# Driver.net
KiCad netlist of a schematic drawn in EAGLE
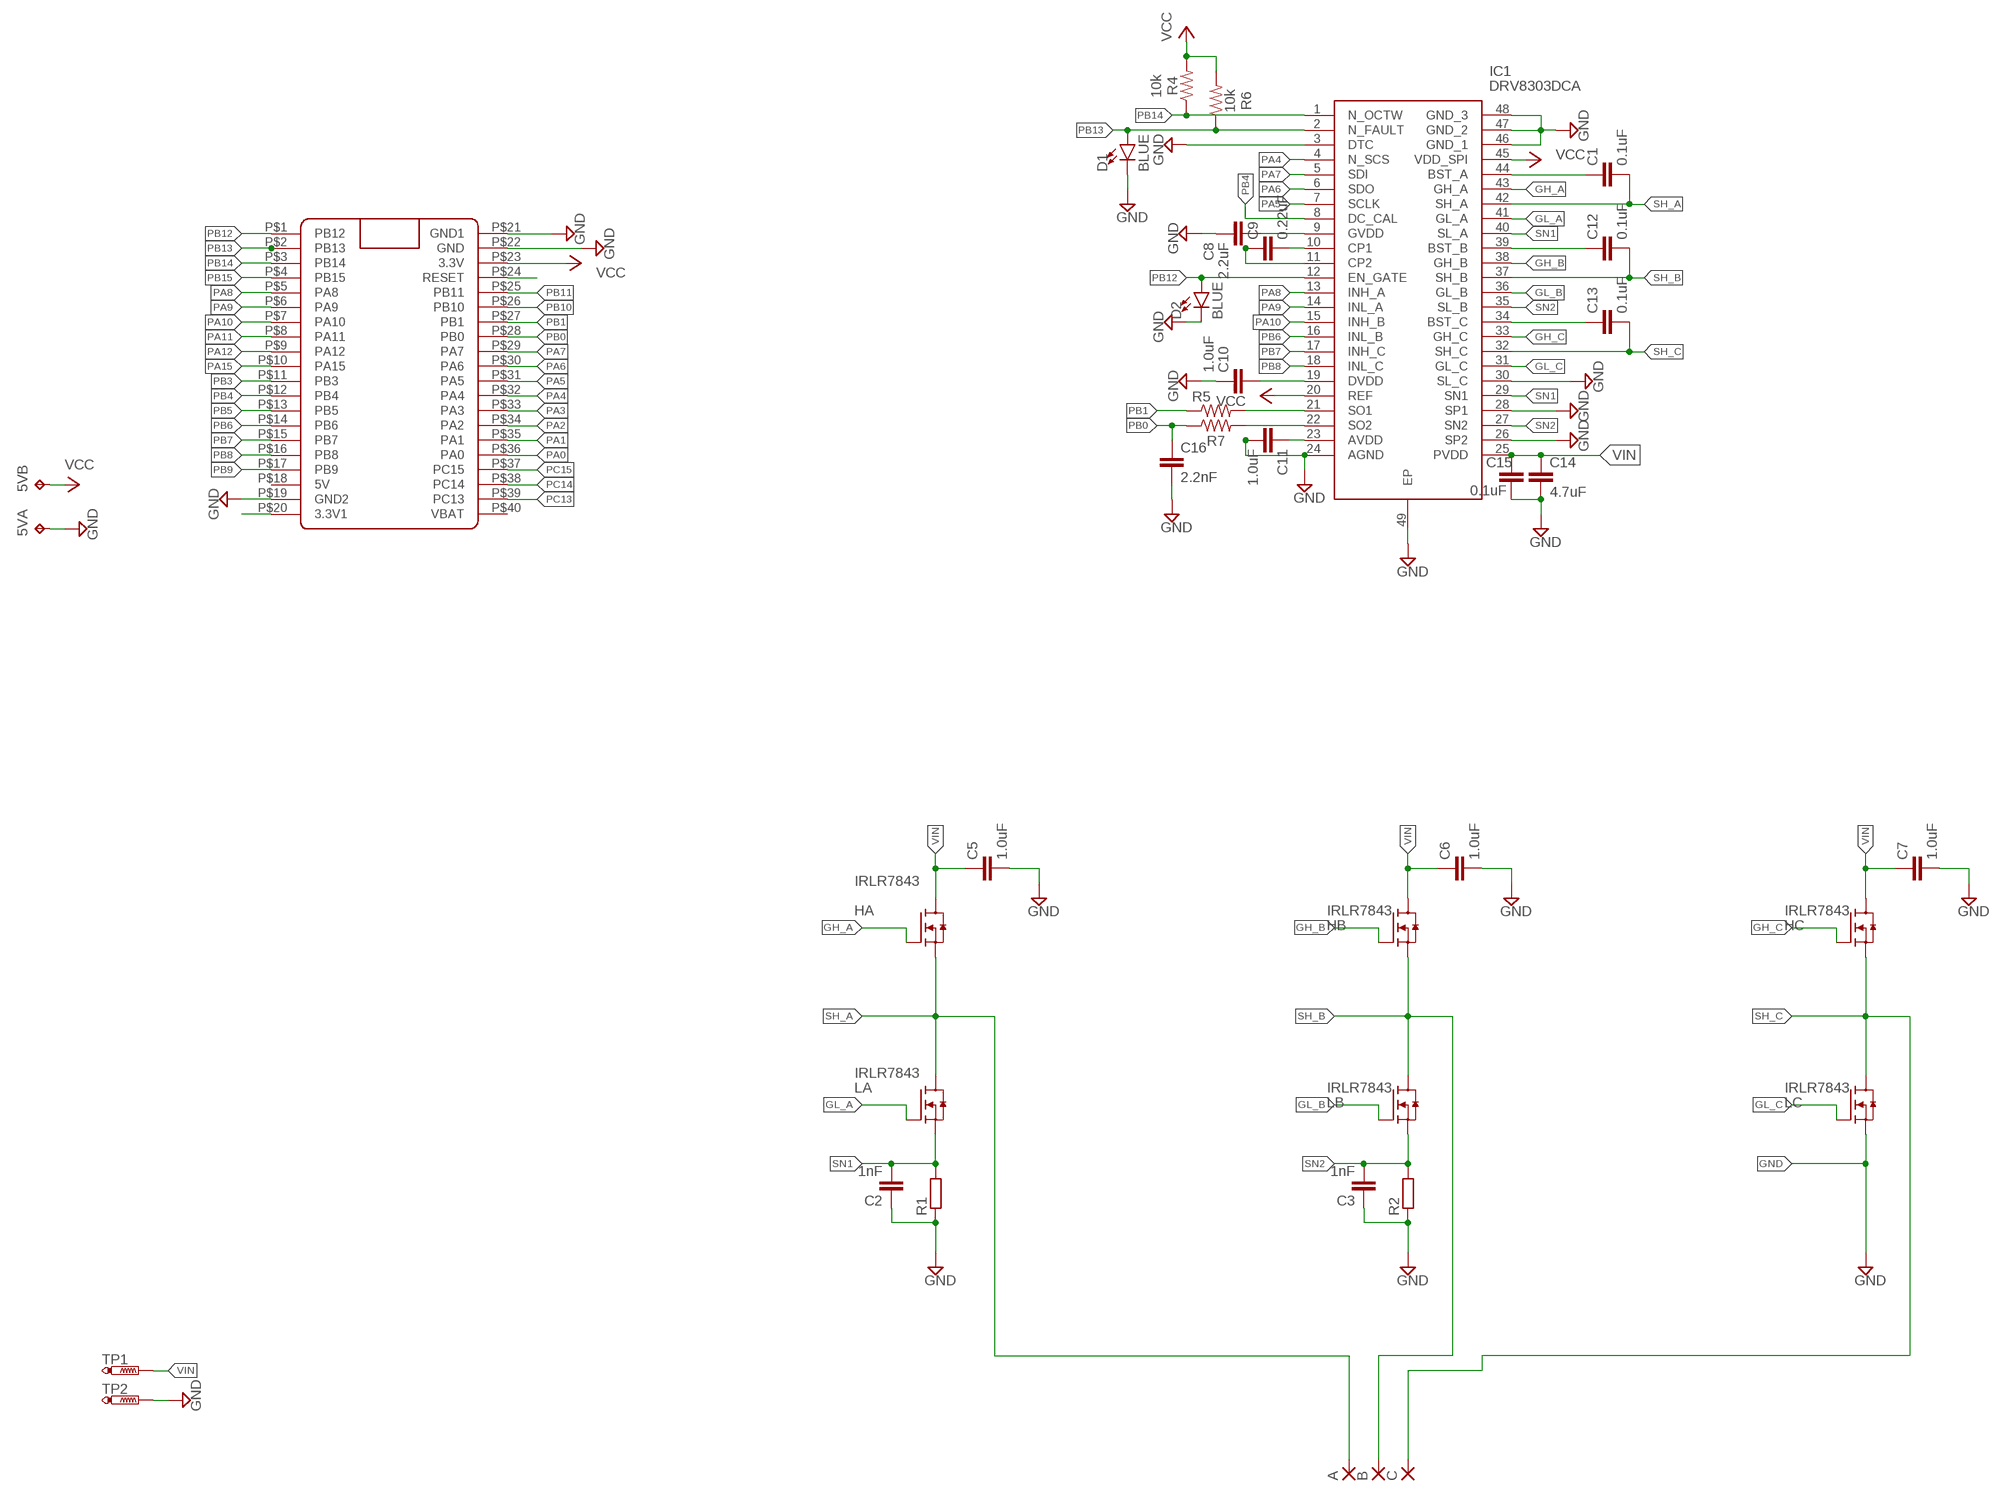
[diagram p0: schematic, sheet 1]

(export (version "E")
  (design (tool "Eeschema 10.0.6"))
  (components
    (comp (ref "5V")
      (value "TP2P2-38-17")
      (footprint "eagle-import:P2-38-17")
      (libsource (lib "eagle-import") (part "TP2P2-38-17"))
    )
    (comp (ref "A")
      (value "SMD5")
      (footprint "eagle-import:SMD2,54-5,08")
      (libsource (lib "eagle-import") (part "SMD5"))
    )
    (comp (ref "B")
      (value "SMD5")
      (footprint "eagle-import:SMD2,54-5,08")
      (libsource (lib "eagle-import") (part "SMD5"))
    )
    (comp (ref "C")
      (value "SMD5")
      (footprint "eagle-import:SMD2,54-5,08")
      (libsource (lib "eagle-import") (part "SMD5"))
    )
    (comp (ref "C1")
      (value "0.1uF")
      (footprint "eagle-import:0603")
      (libsource (lib "eagle-import") (part "0.1UF-0603-25V-(+80/-20%)"))
    )
    (comp (ref "C2")
      (value "1nF")
      (footprint "eagle-import:0603")
      (libsource (lib "eagle-import") (part "1.0NF/1000PF-0603-50V-10%"))
    )
    (comp (ref "C3")
      (value "1nF")
      (footprint "eagle-import:0603")
      (libsource (lib "eagle-import") (part "1.0NF/1000PF-0603-50V-10%"))
    )
    (comp (ref "C5")
      (value "1.0uF")
      (footprint "eagle-import:0603")
      (libsource (lib "eagle-import") (part "1.0UF-0603-16V-10%-X7R"))
    )
    (comp (ref "C6")
      (value "1.0uF")
      (footprint "eagle-import:0603")
      (libsource (lib "eagle-import") (part "1.0UF-0603-16V-10%-X7R"))
    )
    (comp (ref "C7")
      (value "1.0uF")
      (footprint "eagle-import:0603")
      (libsource (lib "eagle-import") (part "1.0UF-0603-16V-10%-X7R"))
    )
    (comp (ref "C8")
      (value "2.2uF")
      (footprint "eagle-import:0603")
      (libsource (lib "eagle-import") (part "2.2UF-0603-10V-20%"))
    )
    (comp (ref "C9")
      (value "0.22uF")
      (footprint "eagle-import:0603")
      (libsource (lib "eagle-import") (part "0.22UF-0603-25V-10%"))
    )
    (comp (ref "C10")
      (value "1.0uF")
      (footprint "eagle-import:0603")
      (libsource (lib "eagle-import") (part "1.0UF-0603-16V-10%"))
    )
    (comp (ref "C11")
      (value "1.0uF")
      (footprint "eagle-import:0603")
      (libsource (lib "eagle-import") (part "1.0UF-0603-16V-10%"))
    )
    (comp (ref "C12")
      (value "0.1uF")
      (footprint "eagle-import:0603")
      (libsource (lib "eagle-import") (part "0.1UF-0603-25V-(+80/-20%)"))
    )
    (comp (ref "C13")
      (value "0.1uF")
      (footprint "eagle-import:0603")
      (libsource (lib "eagle-import") (part "0.1UF-0603-25V-(+80/-20%)"))
    )
    (comp (ref "C14")
      (value "4.7uF")
      (footprint "eagle-import:0603")
      (libsource (lib "eagle-import") (part "4.7UF-0603-35V-(20%)"))
    )
    (comp (ref "C15")
      (value "0.1uF")
      (footprint "eagle-import:0603")
      (libsource (lib "eagle-import") (part "0.1UF-0603-25V-(+80/-20%)"))
    )
    (comp (ref "C16")
      (value "2.2nF")
      (footprint "eagle-import:0603")
      (libsource (lib "eagle-import") (part "2.2NF/2200PF-0603-50V-10%"))
    )
    (comp (ref "D1")
      (value "BLUE")
      (footprint "eagle-import:LED-0603")
      (libsource (lib "eagle-import") (part "LED-BLUE0603"))
    )
    (comp (ref "D2")
      (value "BLUE")
      (footprint "eagle-import:LED-0603")
      (libsource (lib "eagle-import") (part "LED-BLUE0603"))
    )
    (comp (ref "HA")
      (value "IRLR7843")
      (footprint "eagle-import:TO252")
      (libsource (lib "eagle-import") (part "IRLR7843"))
    )
    (comp (ref "HB")
      (value "IRLR7843")
      (footprint "eagle-import:TO252")
      (libsource (lib "eagle-import") (part "IRLR7843"))
    )
    (comp (ref "HC")
      (value "IRLR7843")
      (footprint "eagle-import:TO252")
      (libsource (lib "eagle-import") (part "IRLR7843"))
    )
    (comp (ref "IC1")
      (value "DRV8303DCA")
      (footprint "eagle-import:SOP50P810X120-49N")
      (fields (field (name "MOUSER_PART_NUMBER") "595-DRV8303DCA"))
      (libsource (lib "eagle-import") (part "DRV8303DCA"))
    )
    (comp (ref "LA")
      (value "IRLR7843")
      (footprint "eagle-import:TO252")
      (libsource (lib "eagle-import") (part "IRLR7843"))
    )
    (comp (ref "LB")
      (value "IRLR7843")
      (footprint "eagle-import:TO252")
      (libsource (lib "eagle-import") (part "IRLR7843"))
    )
    (comp (ref "LC")
      (value "IRLR7843")
      (footprint "eagle-import:TO252")
      (libsource (lib "eagle-import") (part "IRLR7843"))
    )
    (comp (ref "R1")
      (value "R-EU_R2512")
      (footprint "eagle-import:R2512")
      (libsource (lib "eagle-import") (part "R-EU_R2512"))
    )
    (comp (ref "R2")
      (value "R-EU_R2512")
      (footprint "eagle-import:R2512")
      (libsource (lib "eagle-import") (part "R-EU_R2512"))
    )
    (comp (ref "R4")
      (value "10k")
      (footprint "eagle-import:0603")
      (libsource (lib "eagle-import") (part "10KOHM-0603-1/10W-1%"))
    )
    (comp (ref "R5")
      (value "0")
      (footprint "eagle-import:0603")
      (libsource (lib "eagle-import") (part "0OHM-0603-1/10W"))
    )
    (comp (ref "R6")
      (value "10k")
      (footprint "eagle-import:0603")
      (libsource (lib "eagle-import") (part "10KOHM-0603-1/10W-1%"))
    )
    (comp (ref "R7")
      (value "0")
      (footprint "eagle-import:0603")
      (libsource (lib "eagle-import") (part "0OHM-0603-1/10W"))
    )
    (comp (ref "TP1")
      (value "PTR1PAD1-20Y")
      (footprint "eagle-import:P1-20Y")
      (libsource (lib "eagle-import") (part "PTR1PAD1-20Y"))
    )
    (comp (ref "TP2")
      (value "PTR1PAD1-20Y")
      (footprint "eagle-import:P1-20Y")
      (libsource (lib "eagle-import") (part "PTR1PAD1-20Y"))
    )
    (comp (ref "U$1")
      (value "BLUE_PILLADVANCED")
      (footprint "eagle-import:BLUE_PILL_ADV")
      (libsource (lib "eagle-import") (part "BLUE_PILLADVANCED"))
    )
  )
  (nets
    (net (code "1") (name "GH_A") (class "Default")
      (node (ref "HA") (pin "1") (pinfunction "G_1") (pintype "passive"))
      (node (ref "IC1") (pin "43") (pinfunction "GH_A_43") (pintype "output"))
    )
    (net (code "2") (name "GH_B") (class "Default")
      (node (ref "HB") (pin "1") (pinfunction "G_1") (pintype "passive"))
      (node (ref "IC1") (pin "38") (pinfunction "GH_B_38") (pintype "output"))
    )
    (net (code "3") (name "GH_C") (class "Default")
      (node (ref "HC") (pin "1") (pinfunction "G_1") (pintype "passive"))
      (node (ref "IC1") (pin "33") (pinfunction "GH_C_33") (pintype "output"))
    )
    (net (code "4") (name "GL_A") (class "Default")
      (node (ref "IC1") (pin "41") (pinfunction "GL_A_41") (pintype "output"))
      (node (ref "LA") (pin "1") (pinfunction "G_1") (pintype "passive"))
    )
    (net (code "5") (name "GL_B") (class "Default")
      (node (ref "IC1") (pin "36") (pinfunction "GL_B_36") (pintype "output"))
      (node (ref "LB") (pin "1") (pinfunction "G_1") (pintype "passive"))
    )
    (net (code "6") (name "GL_C") (class "Default")
      (node (ref "IC1") (pin "31") (pinfunction "GL_C_31") (pintype "output"))
      (node (ref "LC") (pin "1") (pinfunction "G_1") (pintype "passive"))
    )
    (net (code "7") (name "GND") (class "Default")
      (node (ref "5V") (pin "TP-1") (pinfunction "TP_TP-1") (pintype "input"))
      (node (ref "C10") (pin "1") (pinfunction "1_1") (pintype "passive"))
      (node (ref "C11") (pin "2") (pinfunction "2_2") (pintype "passive"))
      (node (ref "C14") (pin "2") (pinfunction "2_2") (pintype "passive"))
      (node (ref "C15") (pin "2") (pinfunction "2_2") (pintype "passive"))
      (node (ref "C16") (pin "2") (pinfunction "2_2") (pintype "passive"))
      (node (ref "C2") (pin "1") (pinfunction "1_1") (pintype "passive"))
      (node (ref "C3") (pin "1") (pinfunction "1_1") (pintype "passive"))
      (node (ref "C5") (pin "2") (pinfunction "2_2") (pintype "passive"))
      (node (ref "C6") (pin "2") (pinfunction "2_2") (pintype "passive"))
      (node (ref "C7") (pin "2") (pinfunction "2_2") (pintype "passive"))
      (node (ref "C8") (pin "2") (pinfunction "2_2") (pintype "passive"))
      (node (ref "D1") (pin "C") (pinfunction "C_C") (pintype "passive"))
      (node (ref "D2") (pin "C") (pinfunction "C_C") (pintype "passive"))
      (node (ref "IC1") (pin "24") (pinfunction "AGND_24") (pintype "power_in"))
      (node (ref "IC1") (pin "26") (pinfunction "SP2_26") (pintype "input"))
      (node (ref "IC1") (pin "28") (pinfunction "SP1_28") (pintype "input"))
      (node (ref "IC1") (pin "3") (pinfunction "DTC_3") (pintype "input"))
      (node (ref "IC1") (pin "30") (pinfunction "SL_C_30") (pintype "input"))
      (node (ref "IC1") (pin "46") (pinfunction "GND_1_46") (pintype "power_in"))
      (node (ref "IC1") (pin "47") (pinfunction "GND_2_47") (pintype "power_in"))
      (node (ref "IC1") (pin "48") (pinfunction "GND_3_48") (pintype "power_in"))
      (node (ref "IC1") (pin "49") (pinfunction "EP_49") (pintype "bidirectional"))
      (node (ref "LC") (pin "2") (pinfunction "S_2") (pintype "passive"))
      (node (ref "R1") (pin "1") (pinfunction "1_1") (pintype "passive"))
      (node (ref "R2") (pin "1") (pinfunction "1_1") (pintype "passive"))
      (node (ref "TP2") (pin "TP") (pinfunction "TP_TP") (pintype "input"))
      (node (ref "U$1") (pin "P$19") (pinfunction "GND2_P$19") (pintype "bidirectional"))
      (node (ref "U$1") (pin "P$21") (pinfunction "GND1_P$21") (pintype "power_in"))
      (node (ref "U$1") (pin "P$22") (pinfunction "GND_P$22") (pintype "bidirectional"))
    )
    (net (code "8") (name "Net-(IC1-AVDD)") (class "Default")
      (node (ref "C11") (pin "1") (pinfunction "1_1") (pintype "passive"))
      (node (ref "IC1") (pin "23") (pinfunction "AVDD_23") (pintype "power_in"))
    )
    (net (code "9") (name "Net-(IC1-BST_A)") (class "Default")
      (node (ref "C1") (pin "1") (pinfunction "1_1") (pintype "passive"))
      (node (ref "IC1") (pin "44") (pinfunction "BST_A_44") (pintype "bidirectional"))
    )
    (net (code "10") (name "Net-(IC1-BST_B)") (class "Default")
      (node (ref "C12") (pin "1") (pinfunction "1_1") (pintype "passive"))
      (node (ref "IC1") (pin "39") (pinfunction "BST_B_39") (pintype "bidirectional"))
    )
    (net (code "11") (name "Net-(IC1-BST_C)") (class "Default")
      (node (ref "C13") (pin "1") (pinfunction "1_1") (pintype "passive"))
      (node (ref "IC1") (pin "34") (pinfunction "BST_C_34") (pintype "bidirectional"))
    )
    (net (code "12") (name "Net-(IC1-CP1)") (class "Default")
      (node (ref "C9") (pin "2") (pinfunction "2_2") (pintype "passive"))
      (node (ref "IC1") (pin "10") (pinfunction "CP1_10") (pintype "power_in"))
    )
    (net (code "13") (name "Net-(IC1-CP2)") (class "Default")
      (node (ref "C9") (pin "1") (pinfunction "1_1") (pintype "passive"))
      (node (ref "IC1") (pin "11") (pinfunction "CP2_11") (pintype "power_in"))
    )
    (net (code "14") (name "Net-(IC1-DVDD)") (class "Default")
      (node (ref "C10") (pin "2") (pinfunction "2_2") (pintype "passive"))
      (node (ref "IC1") (pin "19") (pinfunction "DVDD_19") (pintype "power_in"))
    )
    (net (code "15") (name "Net-(IC1-GVDD)") (class "Default")
      (node (ref "C8") (pin "1") (pinfunction "1_1") (pintype "passive"))
      (node (ref "IC1") (pin "9") (pinfunction "GVDD_9") (pintype "power_in"))
    )
    (net (code "16") (name "Net-(IC1-SO1)") (class "Default")
      (node (ref "IC1") (pin "21") (pinfunction "SO1_21") (pintype "output"))
      (node (ref "R5") (pin "2") (pinfunction "2_2") (pintype "passive"))
    )
    (net (code "17") (name "Net-(IC1-SO2)") (class "Default")
      (node (ref "IC1") (pin "22") (pinfunction "SO2_22") (pintype "output"))
      (node (ref "R7") (pin "2") (pinfunction "2_2") (pintype "passive"))
    )
    (net (code "18") (name "PA0") (class "Default")
      (node (ref "U$1") (pin "P$36") (pinfunction "PA0_P$36") (pintype "bidirectional"))
    )
    (net (code "19") (name "PA1") (class "Default")
      (node (ref "U$1") (pin "P$35") (pinfunction "PA1_P$35") (pintype "bidirectional"))
    )
    (net (code "20") (name "PA2") (class "Default")
      (node (ref "U$1") (pin "P$34") (pinfunction "PA2_P$34") (pintype "bidirectional"))
    )
    (net (code "21") (name "PA3") (class "Default")
      (node (ref "U$1") (pin "P$33") (pinfunction "PA3_P$33") (pintype "bidirectional"))
    )
    (net (code "22") (name "PA4") (class "Default")
      (node (ref "IC1") (pin "4") (pinfunction "N_SCS_4") (pintype "input"))
      (node (ref "U$1") (pin "P$32") (pinfunction "PA4_P$32") (pintype "bidirectional"))
    )
    (net (code "23") (name "PA5") (class "Default")
      (node (ref "IC1") (pin "7") (pinfunction "SCLK_7") (pintype "input"))
      (node (ref "U$1") (pin "P$31") (pinfunction "PA5_P$31") (pintype "bidirectional"))
    )
    (net (code "24") (name "PA6") (class "Default")
      (node (ref "IC1") (pin "6") (pinfunction "SDO_6") (pintype "output"))
      (node (ref "U$1") (pin "P$30") (pinfunction "PA6_P$30") (pintype "bidirectional"))
    )
    (net (code "25") (name "PA7") (class "Default")
      (node (ref "IC1") (pin "5") (pinfunction "SDI_5") (pintype "input"))
      (node (ref "U$1") (pin "P$29") (pinfunction "PA7_P$29") (pintype "bidirectional"))
    )
    (net (code "26") (name "PA8") (class "Default")
      (node (ref "IC1") (pin "13") (pinfunction "INH_A_13") (pintype "input"))
      (node (ref "U$1") (pin "P$5") (pinfunction "PA8_P$5") (pintype "bidirectional"))
    )
    (net (code "27") (name "PA9") (class "Default")
      (node (ref "IC1") (pin "14") (pinfunction "INL_A_14") (pintype "input"))
      (node (ref "U$1") (pin "P$6") (pinfunction "PA9_P$6") (pintype "bidirectional"))
    )
    (net (code "28") (name "PA10") (class "Default")
      (node (ref "IC1") (pin "15") (pinfunction "INH_B_15") (pintype "input"))
      (node (ref "U$1") (pin "P$7") (pinfunction "PA10_P$7") (pintype "bidirectional"))
    )
    (net (code "29") (name "PA11") (class "Default")
      (node (ref "U$1") (pin "P$8") (pinfunction "PA11_P$8") (pintype "bidirectional"))
    )
    (net (code "30") (name "PA12") (class "Default")
      (node (ref "U$1") (pin "P$9") (pinfunction "PA12_P$9") (pintype "bidirectional"))
    )
    (net (code "31") (name "PA15") (class "Default")
      (node (ref "U$1") (pin "P$10") (pinfunction "PA15_P$10") (pintype "bidirectional"))
    )
    (net (code "32") (name "PB0") (class "Default")
      (node (ref "C16") (pin "1") (pinfunction "1_1") (pintype "passive"))
      (node (ref "R7") (pin "1") (pinfunction "1_1") (pintype "passive"))
      (node (ref "U$1") (pin "P$28") (pinfunction "PB0_P$28") (pintype "bidirectional"))
    )
    (net (code "33") (name "PB1") (class "Default")
      (node (ref "R5") (pin "1") (pinfunction "1_1") (pintype "passive"))
      (node (ref "U$1") (pin "P$27") (pinfunction "PB1_P$27") (pintype "bidirectional"))
    )
    (net (code "34") (name "PB3") (class "Default")
      (node (ref "U$1") (pin "P$11") (pinfunction "PB3_P$11") (pintype "bidirectional"))
    )
    (net (code "35") (name "PB4") (class "Default")
      (node (ref "IC1") (pin "8") (pinfunction "DC_CAL_8") (pintype "input"))
      (node (ref "U$1") (pin "P$12") (pinfunction "PB4_P$12") (pintype "bidirectional"))
    )
    (net (code "36") (name "PB5") (class "Default")
      (node (ref "U$1") (pin "P$13") (pinfunction "PB5_P$13") (pintype "bidirectional"))
    )
    (net (code "37") (name "PB6") (class "Default")
      (node (ref "IC1") (pin "16") (pinfunction "INL_B_16") (pintype "input"))
      (node (ref "U$1") (pin "P$14") (pinfunction "PB6_P$14") (pintype "bidirectional"))
    )
    (net (code "38") (name "PB7") (class "Default")
      (node (ref "IC1") (pin "17") (pinfunction "INH_C_17") (pintype "input"))
      (node (ref "U$1") (pin "P$15") (pinfunction "PB7_P$15") (pintype "bidirectional"))
    )
    (net (code "39") (name "PB8") (class "Default")
      (node (ref "IC1") (pin "18") (pinfunction "INL_C_18") (pintype "input"))
      (node (ref "U$1") (pin "P$16") (pinfunction "PB8_P$16") (pintype "bidirectional"))
    )
    (net (code "40") (name "PB9") (class "Default")
      (node (ref "U$1") (pin "P$17") (pinfunction "PB9_P$17") (pintype "bidirectional"))
    )
    (net (code "41") (name "PB10") (class "Default")
      (node (ref "U$1") (pin "P$26") (pinfunction "PB10_P$26") (pintype "bidirectional"))
    )
    (net (code "42") (name "PB11") (class "Default")
      (node (ref "U$1") (pin "P$25") (pinfunction "PB11_P$25") (pintype "bidirectional"))
    )
    (net (code "43") (name "PB12") (class "Default")
      (node (ref "D2") (pin "A") (pinfunction "A_A") (pintype "passive"))
      (node (ref "IC1") (pin "12") (pinfunction "EN_GATE_12") (pintype "input"))
      (node (ref "U$1") (pin "P$1") (pinfunction "PB12_P$1") (pintype "bidirectional"))
    )
    (net (code "44") (name "PB13") (class "Default")
      (node (ref "D1") (pin "A") (pinfunction "A_A") (pintype "passive"))
      (node (ref "IC1") (pin "2") (pinfunction "N_FAULT_2") (pintype "output"))
      (node (ref "R6") (pin "1") (pinfunction "1_1") (pintype "passive"))
      (node (ref "U$1") (pin "P$2") (pinfunction "PB13_P$2") (pintype "bidirectional"))
    )
    (net (code "45") (name "PB14") (class "Default")
      (node (ref "IC1") (pin "1") (pinfunction "N_OCTW_1") (pintype "output"))
      (node (ref "R4") (pin "1") (pinfunction "1_1") (pintype "passive"))
      (node (ref "U$1") (pin "P$3") (pinfunction "PB14_P$3") (pintype "bidirectional"))
    )
    (net (code "46") (name "PB15") (class "Default")
      (node (ref "U$1") (pin "P$4") (pinfunction "PB15_P$4") (pintype "bidirectional"))
    )
    (net (code "47") (name "PC13") (class "Default")
      (node (ref "U$1") (pin "P$39") (pinfunction "PC13_P$39") (pintype "bidirectional"))
    )
    (net (code "48") (name "PC14") (class "Default")
      (node (ref "U$1") (pin "P$38") (pinfunction "PC14_P$38") (pintype "bidirectional"))
    )
    (net (code "49") (name "PC15") (class "Default")
      (node (ref "U$1") (pin "P$37") (pinfunction "PC15_P$37") (pintype "bidirectional"))
    )
    (net (code "50") (name "SH_A") (class "Default")
      (node (ref "A") (pin "1") (pinfunction "P_1") (pintype "passive"))
      (node (ref "C1") (pin "2") (pinfunction "2_2") (pintype "passive"))
      (node (ref "HA") (pin "2") (pinfunction "S_2") (pintype "passive"))
      (node (ref "IC1") (pin "42") (pinfunction "SH_A_42") (pintype "input"))
      (node (ref "LA") (pin "3") (pinfunction "D_3") (pintype "passive"))
    )
    (net (code "51") (name "SH_B") (class "Default")
      (node (ref "B") (pin "1") (pinfunction "P_1") (pintype "passive"))
      (node (ref "C12") (pin "2") (pinfunction "2_2") (pintype "passive"))
      (node (ref "HB") (pin "2") (pinfunction "S_2") (pintype "passive"))
      (node (ref "IC1") (pin "37") (pinfunction "SH_B_37") (pintype "input"))
      (node (ref "LB") (pin "3") (pinfunction "D_3") (pintype "passive"))
    )
    (net (code "52") (name "SH_C") (class "Default")
      (node (ref "C") (pin "1") (pinfunction "P_1") (pintype "passive"))
      (node (ref "C13") (pin "2") (pinfunction "2_2") (pintype "passive"))
      (node (ref "HC") (pin "2") (pinfunction "S_2") (pintype "passive"))
      (node (ref "IC1") (pin "32") (pinfunction "SH_C_32") (pintype "input"))
      (node (ref "LC") (pin "3") (pinfunction "D_3") (pintype "passive"))
    )
    (net (code "53") (name "SN1") (class "Default")
      (node (ref "C2") (pin "2") (pinfunction "2_2") (pintype "passive"))
      (node (ref "IC1") (pin "29") (pinfunction "SN1_29") (pintype "input"))
      (node (ref "IC1") (pin "40") (pinfunction "SL_A_40") (pintype "input"))
      (node (ref "LA") (pin "2") (pinfunction "S_2") (pintype "passive"))
      (node (ref "R1") (pin "2") (pinfunction "2_2") (pintype "passive"))
    )
    (net (code "54") (name "SN2") (class "Default")
      (node (ref "C3") (pin "2") (pinfunction "2_2") (pintype "passive"))
      (node (ref "IC1") (pin "27") (pinfunction "SN2_27") (pintype "input"))
      (node (ref "IC1") (pin "35") (pinfunction "SL_B_35") (pintype "input"))
      (node (ref "LB") (pin "2") (pinfunction "S_2") (pintype "passive"))
      (node (ref "R2") (pin "2") (pinfunction "2_2") (pintype "passive"))
    )
    (net (code "55") (name "VCC") (class "Default")
      (node (ref "5V") (pin "TP-2") (pinfunction "TP_TP-2") (pintype "input"))
      (node (ref "IC1") (pin "20") (pinfunction "REF_20") (pintype "input"))
      (node (ref "IC1") (pin "45") (pinfunction "VDD_SPI_45") (pintype "power_in"))
      (node (ref "R4") (pin "2") (pinfunction "2_2") (pintype "passive"))
      (node (ref "R6") (pin "2") (pinfunction "2_2") (pintype "passive"))
      (node (ref "U$1") (pin "P$23") (pinfunction "3.3V_P$23") (pintype "bidirectional"))
    )
    (net (code "56") (name "VIN") (class "Default")
      (node (ref "C14") (pin "1") (pinfunction "1_1") (pintype "passive"))
      (node (ref "C15") (pin "1") (pinfunction "1_1") (pintype "passive"))
      (node (ref "C5") (pin "1") (pinfunction "1_1") (pintype "passive"))
      (node (ref "C6") (pin "1") (pinfunction "1_1") (pintype "passive"))
      (node (ref "C7") (pin "1") (pinfunction "1_1") (pintype "passive"))
      (node (ref "HA") (pin "3") (pinfunction "D_3") (pintype "passive"))
      (node (ref "HB") (pin "3") (pinfunction "D_3") (pintype "passive"))
      (node (ref "HC") (pin "3") (pinfunction "D_3") (pintype "passive"))
      (node (ref "IC1") (pin "25") (pinfunction "PVDD_25") (pintype "power_in"))
      (node (ref "TP1") (pin "TP") (pinfunction "TP_TP") (pintype "input"))
    )
    (net (code "57") (name "unconnected-(U$1-3.3V1-PadP$20)") (class "Default")
      (node (ref "U$1") (pin "P$20") (pinfunction "3.3V1_P$20") (pintype "bidirectional"))
    )
    (net (code "58") (name "unconnected-(U$1-5V-PadP$18)") (class "Default")
      (node (ref "U$1") (pin "P$18") (pinfunction "5V_P$18") (pintype "bidirectional"))
    )
    (net (code "59") (name "unconnected-(U$1-RESET-PadP$24)") (class "Default")
      (node (ref "U$1") (pin "P$24") (pinfunction "RESET_P$24") (pintype "bidirectional"))
    )
    (net (code "60") (name "unconnected-(U$1-VBAT-PadP$40)") (class "Default")
      (node (ref "U$1") (pin "P$40") (pinfunction "VBAT_P$40") (pintype "bidirectional"))
    )
  )
)
